# untitled.net
KiCad netlist of a schematic drawn in EAGLE
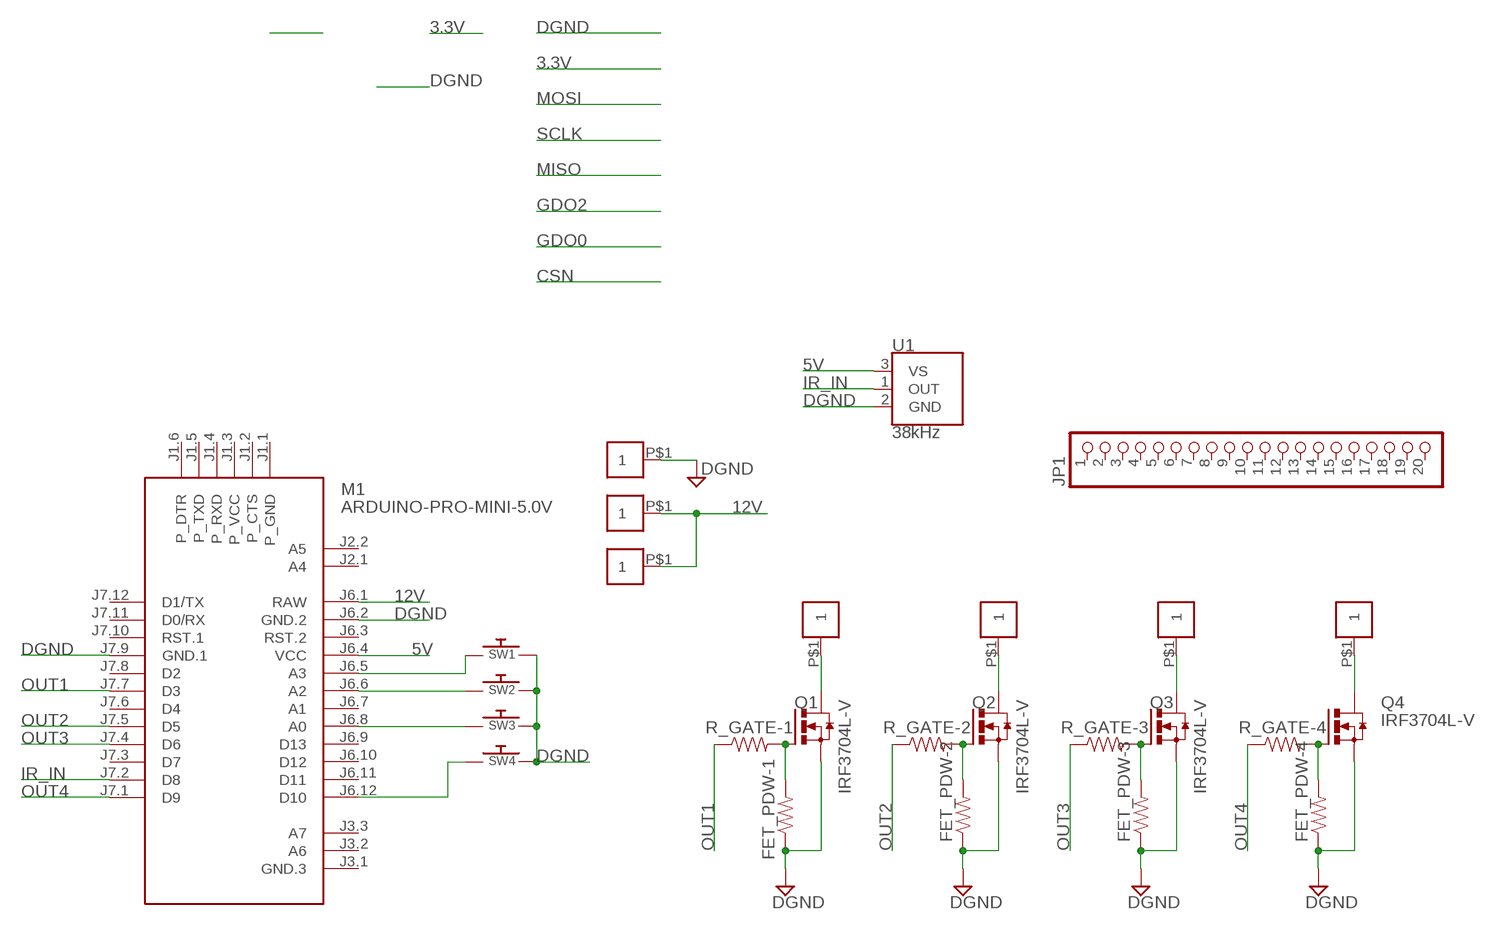
[diagram p0: schematic, sheet 1]

(export (version "E")
  (design (tool "Eeschema 10.0.6"))
  (components
    (comp (ref "FET_PDW-1")
      (value "RESISTOR0603-RES")
      (footprint "eagle-import:0603-RES")
      (libsource (lib "eagle-import") (part "RESISTOR0603-RES"))
    )
    (comp (ref "FET_PDW-2")
      (value "RESISTOR0603-RES")
      (footprint "eagle-import:0603-RES")
      (libsource (lib "eagle-import") (part "RESISTOR0603-RES"))
    )
    (comp (ref "FET_PDW-3")
      (value "RESISTOR0603-RES")
      (footprint "eagle-import:0603-RES")
      (libsource (lib "eagle-import") (part "RESISTOR0603-RES"))
    )
    (comp (ref "FET_PDW-4")
      (value "RESISTOR0603-RES")
      (footprint "eagle-import:0603-RES")
      (libsource (lib "eagle-import") (part "RESISTOR0603-RES"))
    )
    (comp (ref "JP1")
      (value "PINHD-1X20")
      (footprint "eagle-import:1X20")
      (libsource (lib "eagle-import") (part "PINHD-1X20"))
    )
    (comp (ref "M1")
      (value "ARDUINO-PRO-MINI-5.0V")
      (footprint "eagle-import:ARDUINO-PRO-MINI")
      (libsource (lib "eagle-import") (part "ARDUINO-PRO-MINI-5.0V"))
    )
    (comp (ref "Q1")
      (value "IRF3704L-V")
      (footprint "eagle-import:TO262-V")
      (libsource (lib "eagle-import") (part "IRF3704L-V"))
    )
    (comp (ref "Q2")
      (value "IRF3704L-V")
      (footprint "eagle-import:TO262-V")
      (libsource (lib "eagle-import") (part "IRF3704L-V"))
    )
    (comp (ref "Q3")
      (value "IRF3704L-V")
      (footprint "eagle-import:TO262-V")
      (libsource (lib "eagle-import") (part "IRF3704L-V"))
    )
    (comp (ref "Q4")
      (value "IRF3704L-V")
      (footprint "eagle-import:TO262-V")
      (libsource (lib "eagle-import") (part "IRF3704L-V"))
    )
    (comp (ref "R_GATE-1")
      (value "RESISTOR0603-RES")
      (footprint "eagle-import:0603-RES")
      (libsource (lib "eagle-import") (part "RESISTOR0603-RES"))
    )
    (comp (ref "R_GATE-2")
      (value "RESISTOR0603-RES")
      (footprint "eagle-import:0603-RES")
      (libsource (lib "eagle-import") (part "RESISTOR0603-RES"))
    )
    (comp (ref "R_GATE-3")
      (value "RESISTOR0603-RES")
      (footprint "eagle-import:0603-RES")
      (libsource (lib "eagle-import") (part "RESISTOR0603-RES"))
    )
    (comp (ref "R_GATE-4")
      (value "RESISTOR0603-RES")
      (footprint "eagle-import:0603-RES")
      (libsource (lib "eagle-import") (part "RESISTOR0603-RES"))
    )
    (comp (ref "SW1")
      (value "SWITCH_PUSHBUTTONC&K_KSS")
      (footprint "eagle-import:BTN_CK_KSS")
      (libsource (lib "eagle-import") (part "SWITCH_PUSHBUTTONC&K_KSS"))
    )
    (comp (ref "SW2")
      (value "SWITCH_PUSHBUTTONC&K_KSS")
      (footprint "eagle-import:BTN_CK_KSS")
      (libsource (lib "eagle-import") (part "SWITCH_PUSHBUTTONC&K_KSS"))
    )
    (comp (ref "SW3")
      (value "SWITCH_PUSHBUTTONC&K_KSS")
      (footprint "eagle-import:BTN_CK_KSS")
      (libsource (lib "eagle-import") (part "SWITCH_PUSHBUTTONC&K_KSS"))
    )
    (comp (ref "SW4")
      (value "SWITCH_PUSHBUTTONC&K_KSS")
      (footprint "eagle-import:BTN_CK_KSS")
      (libsource (lib "eagle-import") (part "SWITCH_PUSHBUTTONC&K_KSS"))
    )
    (comp (ref "U$2")
      (value "1X01_2.54MM")
      (footprint "eagle-import:1X01_2.54MM")
      (libsource (lib "eagle-import") (part "1X01_2.54MM"))
    )
    (comp (ref "U$3")
      (value "1X01_2.54MM")
      (footprint "eagle-import:1X01_2.54MM")
      (libsource (lib "eagle-import") (part "1X01_2.54MM"))
    )
    (comp (ref "U$4")
      (value "1X01_2.54MM")
      (footprint "eagle-import:1X01_2.54MM")
      (libsource (lib "eagle-import") (part "1X01_2.54MM"))
    )
    (comp (ref "U$5")
      (value "1X01_2.54MM")
      (footprint "eagle-import:1X01_2.54MM")
      (libsource (lib "eagle-import") (part "1X01_2.54MM"))
    )
    (comp (ref "U$6")
      (value "1X01_2.54MM")
      (footprint "eagle-import:1X01_2.54MM")
      (libsource (lib "eagle-import") (part "1X01_2.54MM"))
    )
    (comp (ref "U$7")
      (value "1X01_2.54MM")
      (footprint "eagle-import:1X01_2.54MM")
      (libsource (lib "eagle-import") (part "1X01_2.54MM"))
    )
    (comp (ref "U$8")
      (value "1X01_2.54MM")
      (footprint "eagle-import:1X01_2.54MM")
      (libsource (lib "eagle-import") (part "1X01_2.54MM"))
    )
    (comp (ref "U1")
      (value "38kHz")
      (footprint "eagle-import:TSOP382")
      (libsource (lib "eagle-import") (part "TSOP38238"))
    )
  )
  (nets
    (net (code "2") (name "/5V") (class "Default")
      (node (ref "M1") (pin "J6.4") (pinfunction "VCC_J6.4") (pintype "power_in"))
      (node (ref "U1") (pin "3") (pinfunction "VS_3") (pintype "bidirectional"))
    )
    (net (code "3") (name "/12V") (class "Default")
      (node (ref "M1") (pin "J6.1") (pinfunction "RAW_J6.1") (pintype "power_in"))
      (node (ref "U$5") (pin "P$1") (pinfunction "1_P$1") (pintype "bidirectional"))
      (node (ref "U$8") (pin "P$1") (pinfunction "1_P$1") (pintype "bidirectional"))
    )
    (net (code "7") (name "/IR_IN") (class "Default")
      (node (ref "M1") (pin "J7.2") (pinfunction "D8_J7.2") (pintype "bidirectional"))
      (node (ref "U1") (pin "1") (pinfunction "OUT_1") (pintype "bidirectional"))
    )
    (net (code "10") (name "/OUT1") (class "Default")
      (node (ref "M1") (pin "J7.7") (pinfunction "D3_J7.7") (pintype "bidirectional"))
      (node (ref "R_GATE-1") (pin "1") (pinfunction "1_1") (pintype "passive"))
    )
    (net (code "11") (name "/OUT2") (class "Default")
      (node (ref "M1") (pin "J7.5") (pinfunction "D5_J7.5") (pintype "bidirectional"))
      (node (ref "R_GATE-2") (pin "1") (pinfunction "1_1") (pintype "passive"))
    )
    (net (code "12") (name "/OUT3") (class "Default")
      (node (ref "M1") (pin "J7.4") (pinfunction "D6_J7.4") (pintype "bidirectional"))
      (node (ref "R_GATE-3") (pin "1") (pinfunction "1_1") (pintype "passive"))
    )
    (net (code "13") (name "/OUT4") (class "Default")
      (node (ref "M1") (pin "J7.1") (pinfunction "D9_J7.1") (pintype "bidirectional"))
      (node (ref "R_GATE-4") (pin "1") (pinfunction "1_1") (pintype "passive"))
    )
    (net (code "15") (name "DGND") (class "Default")
      (node (ref "FET_PDW-1") (pin "1") (pinfunction "1_1") (pintype "passive"))
      (node (ref "FET_PDW-2") (pin "1") (pinfunction "1_1") (pintype "passive"))
      (node (ref "FET_PDW-3") (pin "1") (pinfunction "1_1") (pintype "passive"))
      (node (ref "FET_PDW-4") (pin "1") (pinfunction "1_1") (pintype "passive"))
      (node (ref "M1") (pin "J6.2") (pinfunction "GND.2_J6.2") (pintype "power_in"))
      (node (ref "M1") (pin "J7.9") (pinfunction "GND.1_J7.9") (pintype "power_in"))
      (node (ref "Q1") (pin "3") (pinfunction "S_3") (pintype "passive"))
      (node (ref "Q2") (pin "3") (pinfunction "S_3") (pintype "passive"))
      (node (ref "Q3") (pin "3") (pinfunction "S_3") (pintype "passive"))
      (node (ref "Q4") (pin "3") (pinfunction "S_3") (pintype "passive"))
      (node (ref "SW1") (pin "P$2") (pinfunction "P$2_P$2") (pintype "passive"))
      (node (ref "SW2") (pin "P$2") (pinfunction "P$2_P$2") (pintype "passive"))
      (node (ref "SW3") (pin "P$2") (pinfunction "P$2_P$2") (pintype "passive"))
      (node (ref "SW4") (pin "P$2") (pinfunction "P$2_P$2") (pintype "passive"))
      (node (ref "U$7") (pin "P$1") (pinfunction "1_P$1") (pintype "bidirectional"))
      (node (ref "U1") (pin "2") (pinfunction "GND_2") (pintype "bidirectional"))
    )
    (net (code "16") (name "Net-(M1-A0)") (class "Default")
      (node (ref "M1") (pin "J6.8") (pinfunction "A0_J6.8") (pintype "bidirectional"))
      (node (ref "SW3") (pin "P$1") (pinfunction "P$1_P$1") (pintype "passive"))
    )
    (net (code "17") (name "Net-(M1-A2)") (class "Default")
      (node (ref "M1") (pin "J6.6") (pinfunction "A2_J6.6") (pintype "bidirectional"))
      (node (ref "SW2") (pin "P$1") (pinfunction "P$1_P$1") (pintype "passive"))
    )
    (net (code "18") (name "Net-(M1-A3)") (class "Default")
      (node (ref "M1") (pin "J6.5") (pinfunction "A3_J6.5") (pintype "bidirectional"))
      (node (ref "SW1") (pin "P$1") (pinfunction "P$1_P$1") (pintype "passive"))
    )
    (net (code "19") (name "Net-(M1-D10)") (class "Default")
      (node (ref "M1") (pin "J6.12") (pinfunction "D10_J6.12") (pintype "bidirectional"))
      (node (ref "SW4") (pin "P$1") (pinfunction "P$1_P$1") (pintype "passive"))
    )
    (net (code "20") (name "Net-(Q1-D)") (class "Default")
      (node (ref "Q1") (pin "2") (pinfunction "D_2") (pintype "passive"))
      (node (ref "U$2") (pin "P$1") (pinfunction "1_P$1") (pintype "bidirectional"))
    )
    (net (code "21") (name "Net-(Q1-G)") (class "Default")
      (node (ref "FET_PDW-1") (pin "2") (pinfunction "2_2") (pintype "passive"))
      (node (ref "Q1") (pin "1") (pinfunction "G_1") (pintype "passive"))
      (node (ref "R_GATE-1") (pin "2") (pinfunction "2_2") (pintype "passive"))
    )
    (net (code "22") (name "Net-(Q2-D)") (class "Default")
      (node (ref "Q2") (pin "2") (pinfunction "D_2") (pintype "passive"))
      (node (ref "U$3") (pin "P$1") (pinfunction "1_P$1") (pintype "bidirectional"))
    )
    (net (code "23") (name "Net-(Q2-G)") (class "Default")
      (node (ref "FET_PDW-2") (pin "2") (pinfunction "2_2") (pintype "passive"))
      (node (ref "Q2") (pin "1") (pinfunction "G_1") (pintype "passive"))
      (node (ref "R_GATE-2") (pin "2") (pinfunction "2_2") (pintype "passive"))
    )
    (net (code "24") (name "Net-(Q3-D)") (class "Default")
      (node (ref "Q3") (pin "2") (pinfunction "D_2") (pintype "passive"))
      (node (ref "U$4") (pin "P$1") (pinfunction "1_P$1") (pintype "bidirectional"))
    )
    (net (code "25") (name "Net-(Q3-G)") (class "Default")
      (node (ref "FET_PDW-3") (pin "2") (pinfunction "2_2") (pintype "passive"))
      (node (ref "Q3") (pin "1") (pinfunction "G_1") (pintype "passive"))
      (node (ref "R_GATE-3") (pin "2") (pinfunction "2_2") (pintype "passive"))
    )
    (net (code "26") (name "Net-(Q4-D)") (class "Default")
      (node (ref "Q4") (pin "2") (pinfunction "D_2") (pintype "passive"))
      (node (ref "U$6") (pin "P$1") (pinfunction "1_P$1") (pintype "bidirectional"))
    )
    (net (code "27") (name "Net-(Q4-G)") (class "Default")
      (node (ref "FET_PDW-4") (pin "2") (pinfunction "2_2") (pintype "passive"))
      (node (ref "Q4") (pin "1") (pinfunction "G_1") (pintype "passive"))
      (node (ref "R_GATE-4") (pin "2") (pinfunction "2_2") (pintype "passive"))
    )
    (net (code "28") (name "unconnected-(JP1-Pad1)") (class "Default")
      (node (ref "JP1") (pin "1") (pinfunction "1_1") (pintype "passive"))
    )
    (net (code "29") (name "unconnected-(JP1-Pad2)") (class "Default")
      (node (ref "JP1") (pin "2") (pinfunction "2_2") (pintype "passive"))
    )
    (net (code "30") (name "unconnected-(JP1-Pad3)") (class "Default")
      (node (ref "JP1") (pin "3") (pinfunction "3_3") (pintype "passive"))
    )
    (net (code "31") (name "unconnected-(JP1-Pad4)") (class "Default")
      (node (ref "JP1") (pin "4") (pinfunction "4_4") (pintype "passive"))
    )
    (net (code "32") (name "unconnected-(JP1-Pad5)") (class "Default")
      (node (ref "JP1") (pin "5") (pinfunction "5_5") (pintype "passive"))
    )
    (net (code "33") (name "unconnected-(JP1-Pad6)") (class "Default")
      (node (ref "JP1") (pin "6") (pinfunction "6_6") (pintype "passive"))
    )
    (net (code "34") (name "unconnected-(JP1-Pad7)") (class "Default")
      (node (ref "JP1") (pin "7") (pinfunction "7_7") (pintype "passive"))
    )
    (net (code "35") (name "unconnected-(JP1-Pad8)") (class "Default")
      (node (ref "JP1") (pin "8") (pinfunction "8_8") (pintype "passive"))
    )
    (net (code "36") (name "unconnected-(JP1-Pad9)") (class "Default")
      (node (ref "JP1") (pin "9") (pinfunction "9_9") (pintype "passive"))
    )
    (net (code "37") (name "unconnected-(JP1-Pad10)") (class "Default")
      (node (ref "JP1") (pin "10") (pinfunction "10_10") (pintype "passive"))
    )
    (net (code "38") (name "unconnected-(JP1-Pad11)") (class "Default")
      (node (ref "JP1") (pin "11") (pinfunction "11_11") (pintype "passive"))
    )
    (net (code "39") (name "unconnected-(JP1-Pad12)") (class "Default")
      (node (ref "JP1") (pin "12") (pinfunction "12_12") (pintype "passive"))
    )
    (net (code "40") (name "unconnected-(JP1-Pad13)") (class "Default")
      (node (ref "JP1") (pin "13") (pinfunction "13_13") (pintype "passive"))
    )
    (net (code "41") (name "unconnected-(JP1-Pad14)") (class "Default")
      (node (ref "JP1") (pin "14") (pinfunction "14_14") (pintype "passive"))
    )
    (net (code "42") (name "unconnected-(JP1-Pad15)") (class "Default")
      (node (ref "JP1") (pin "15") (pinfunction "15_15") (pintype "passive"))
    )
    (net (code "43") (name "unconnected-(JP1-Pad16)") (class "Default")
      (node (ref "JP1") (pin "16") (pinfunction "16_16") (pintype "passive"))
    )
    (net (code "44") (name "unconnected-(JP1-Pad17)") (class "Default")
      (node (ref "JP1") (pin "17") (pinfunction "17_17") (pintype "passive"))
    )
    (net (code "45") (name "unconnected-(JP1-Pad18)") (class "Default")
      (node (ref "JP1") (pin "18") (pinfunction "18_18") (pintype "passive"))
    )
    (net (code "46") (name "unconnected-(JP1-Pad19)") (class "Default")
      (node (ref "JP1") (pin "19") (pinfunction "19_19") (pintype "passive"))
    )
    (net (code "47") (name "unconnected-(JP1-Pad20)") (class "Default")
      (node (ref "JP1") (pin "20") (pinfunction "20_20") (pintype "passive"))
    )
    (net (code "48") (name "unconnected-(M1-A1-PadJ6.7)") (class "Default")
      (node (ref "M1") (pin "J6.7") (pinfunction "A1_J6.7") (pintype "bidirectional"))
    )
    (net (code "49") (name "unconnected-(M1-A4-PadJ2.1)") (class "Default")
      (node (ref "M1") (pin "J2.1") (pinfunction "A4_J2.1") (pintype "bidirectional"))
    )
    (net (code "50") (name "unconnected-(M1-A5-PadJ2.2)") (class "Default")
      (node (ref "M1") (pin "J2.2") (pinfunction "A5_J2.2") (pintype "bidirectional"))
    )
    (net (code "51") (name "unconnected-(M1-A6-PadJ3.2)") (class "Default")
      (node (ref "M1") (pin "J3.2") (pinfunction "A6_J3.2") (pintype "bidirectional"))
    )
    (net (code "52") (name "unconnected-(M1-A7-PadJ3.3)") (class "Default")
      (node (ref "M1") (pin "J3.3") (pinfunction "A7_J3.3") (pintype "bidirectional"))
    )
    (net (code "53") (name "unconnected-(M1-D0{slash}RX-PadJ7.11)") (class "Default")
      (node (ref "M1") (pin "J7.11") (pinfunction "D0/RX_J7.11") (pintype "bidirectional"))
    )
    (net (code "54") (name "unconnected-(M1-D1{slash}TX-PadJ7.12)") (class "Default")
      (node (ref "M1") (pin "J7.12") (pinfunction "D1/TX_J7.12") (pintype "bidirectional"))
    )
    (net (code "55") (name "unconnected-(M1-D2-PadJ7.8)") (class "Default")
      (node (ref "M1") (pin "J7.8") (pinfunction "D2_J7.8") (pintype "bidirectional"))
    )
    (net (code "56") (name "unconnected-(M1-D4-PadJ7.6)") (class "Default")
      (node (ref "M1") (pin "J7.6") (pinfunction "D4_J7.6") (pintype "bidirectional"))
    )
    (net (code "57") (name "unconnected-(M1-D7-PadJ7.3)") (class "Default")
      (node (ref "M1") (pin "J7.3") (pinfunction "D7_J7.3") (pintype "bidirectional"))
    )
    (net (code "58") (name "unconnected-(M1-D11-PadJ6.11)") (class "Default")
      (node (ref "M1") (pin "J6.11") (pinfunction "D11_J6.11") (pintype "bidirectional"))
    )
    (net (code "59") (name "unconnected-(M1-D12-PadJ6.10)") (class "Default")
      (node (ref "M1") (pin "J6.10") (pinfunction "D12_J6.10") (pintype "bidirectional"))
    )
    (net (code "60") (name "unconnected-(M1-D13-PadJ6.9)") (class "Default")
      (node (ref "M1") (pin "J6.9") (pinfunction "D13_J6.9") (pintype "bidirectional"))
    )
    (net (code "61") (name "unconnected-(M1-GND.3-PadJ3.1)") (class "Default")
      (node (ref "M1") (pin "J3.1") (pinfunction "GND.3_J3.1") (pintype "bidirectional"))
    )
    (net (code "62") (name "unconnected-(M1-P_CTS-PadJ1.2)") (class "Default")
      (node (ref "M1") (pin "J1.2") (pinfunction "P_CTS_J1.2") (pintype "bidirectional"))
    )
    (net (code "63") (name "unconnected-(M1-P_DTR-PadJ1.6)") (class "Default")
      (node (ref "M1") (pin "J1.6") (pinfunction "P_DTR_J1.6") (pintype "bidirectional"))
    )
    (net (code "64") (name "unconnected-(M1-P_GND-PadJ1.1)") (class "Default")
      (node (ref "M1") (pin "J1.1") (pinfunction "P_GND_J1.1") (pintype "bidirectional"))
    )
    (net (code "65") (name "unconnected-(M1-P_RXD-PadJ1.4)") (class "Default")
      (node (ref "M1") (pin "J1.4") (pinfunction "P_RXD_J1.4") (pintype "bidirectional"))
    )
    (net (code "66") (name "unconnected-(M1-P_TXD-PadJ1.5)") (class "Default")
      (node (ref "M1") (pin "J1.5") (pinfunction "P_TXD_J1.5") (pintype "bidirectional"))
    )
    (net (code "67") (name "unconnected-(M1-P_VCC-PadJ1.3)") (class "Default")
      (node (ref "M1") (pin "J1.3") (pinfunction "P_VCC_J1.3") (pintype "bidirectional"))
    )
    (net (code "68") (name "unconnected-(M1-RST.1-PadJ7.10)") (class "Default")
      (node (ref "M1") (pin "J7.10") (pinfunction "RST.1_J7.10") (pintype "bidirectional"))
    )
    (net (code "69") (name "unconnected-(M1-RST.2-PadJ6.3)") (class "Default")
      (node (ref "M1") (pin "J6.3") (pinfunction "RST.2_J6.3") (pintype "bidirectional"))
    )
  )
)
